# Generator_main.net
KiCad netlist of a schematic drawn in Altium Designer
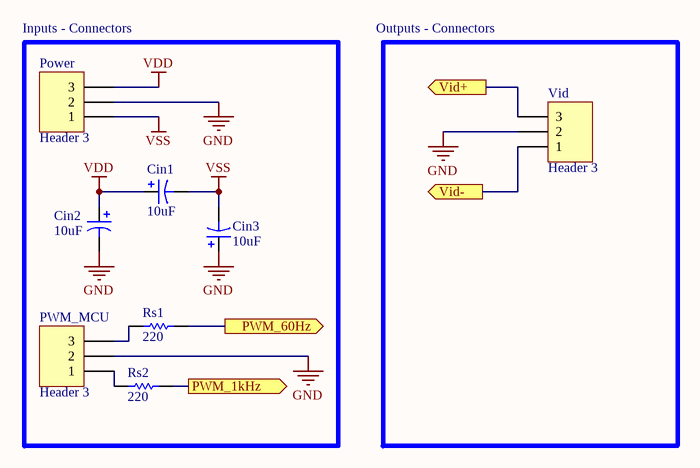
[diagram p0: Generator_main.SchDoc]

(export (version "E")
  (design (tool "Eeschema 10.0.6"))
  (components
    (comp (ref "Cin1")
      (value "10uF")
      (footprint "RB7.6-15")
      (description "Polarized Capacitor (Radial)")
      (fields (field (name "Comment") "Cap Pol1") (field (name "PUBLISHER") "Altium Limited"))
      (libsource (lib "signal-generator") (part "Cap Pol1"))
    )
    (comp (ref "Cin2")
      (value "10uF")
      (footprint "RB7.6-15")
      (description "Polarized Capacitor (Radial)")
      (fields (field (name "Comment") "Cap Pol1") (field (name "PUBLISHER") "Altium Limited"))
      (libsource (lib "signal-generator") (part "Cap Pol1"))
    )
    (comp (ref "Cin3")
      (value "10uF")
      (footprint "RB7.6-15")
      (description "Polarized Capacitor (Radial)")
      (fields (field (name "Comment") "Cap Pol1") (field (name "PUBLISHER") "Altium Limited"))
      (libsource (lib "signal-generator") (part "Cap Pol1"))
    )
    (comp (ref "Power")
      (value "Header 3")
      (footprint "MTA_3M")
      (description "Header, 3-Pin")
      (fields (field (name "PUBLISHER") "Altium Limited"))
      (libsource (lib "signal-generator") (part "Header 3"))
    )
    (comp (ref "PWM_MCU")
      (value "Header 3")
      (footprint "MTA_3M")
      (description "Header, 3-Pin")
      (fields (field (name "PUBLISHER") "Altium Limited"))
      (libsource (lib "signal-generator") (part "Header 3"))
    )
    (comp (ref "Rs1")
      (value "220")
      (footprint "Resistor_Axial 0.4")
      (description "Resistor")
      (fields (field (name "Comment") "Res1") (field (name "PUBLISHER") "Altium Limited"))
      (libsource (lib "signal-generator") (part "Res1"))
    )
    (comp (ref "Rs2")
      (value "220")
      (footprint "Resistor_Axial 0.4")
      (description "Resistor")
      (fields (field (name "Comment") "Res1") (field (name "PUBLISHER") "Altium Limited"))
      (libsource (lib "signal-generator") (part "Res1"))
    )
    (comp (ref "Vid")
      (value "Header 3")
      (footprint "MTA_3M")
      (description "Header, 3-Pin")
      (fields (field (name "PUBLISHER") "Altium Limited"))
      (libsource (lib "") (part "Header 3_1"))
    )
  )
  (nets
    (net (code "1") (name "/PWM_1kHz") (class "Default")
      (node (ref "Rs2") (pin "2") (pinfunction "2_2") (pintype "passive"))
    )
    (net (code "2") (name "/PWM_60Hz") (class "Default")
      (node (ref "Rs1") (pin "2") (pinfunction "2_2") (pintype "passive"))
    )
    (net (code "3") (name "/Vid+") (class "Default")
      (node (ref "Vid") (pin "3") (pinfunction "3_3") (pintype "passive"))
    )
    (net (code "4") (name "/Vid-") (class "Default")
      (node (ref "Vid") (pin "1") (pinfunction "1_1") (pintype "passive"))
    )
    (net (code "5") (name "GND") (class "Default")
      (node (ref "Cin2") (pin "2") (pinfunction "2_2") (pintype "passive"))
      (node (ref "Cin3") (pin "1") (pinfunction "1_1") (pintype "passive"))
      (node (ref "PWM_MCU") (pin "2") (pinfunction "2_2") (pintype "passive"))
      (node (ref "Power") (pin "2") (pinfunction "2_2") (pintype "passive"))
      (node (ref "Vid") (pin "2") (pinfunction "2_2") (pintype "passive"))
    )
    (net (code "6") (name "Net-(PWM_MCU-Pad1)") (class "Default")
      (node (ref "PWM_MCU") (pin "1") (pinfunction "1_1") (pintype "passive"))
      (node (ref "Rs2") (pin "1") (pinfunction "1_1") (pintype "passive"))
    )
    (net (code "7") (name "Net-(PWM_MCU-Pad3)") (class "Default")
      (node (ref "PWM_MCU") (pin "3") (pinfunction "3_3") (pintype "passive"))
      (node (ref "Rs1") (pin "1") (pinfunction "1_1") (pintype "passive"))
    )
    (net (code "8") (name "VDD") (class "Default")
      (node (ref "Cin1") (pin "1") (pinfunction "1_1") (pintype "passive"))
      (node (ref "Cin2") (pin "1") (pinfunction "1_1") (pintype "passive"))
      (node (ref "Power") (pin "3") (pinfunction "3_3") (pintype "passive"))
    )
    (net (code "9") (name "VSS") (class "Default")
      (node (ref "Cin1") (pin "2") (pinfunction "2_2") (pintype "passive"))
      (node (ref "Cin3") (pin "2") (pinfunction "2_2") (pintype "passive"))
      (node (ref "Power") (pin "1") (pinfunction "1_1") (pintype "passive"))
    )
  )
)
